# robot.net
KiCad netlist of a schematic drawn in EAGLE
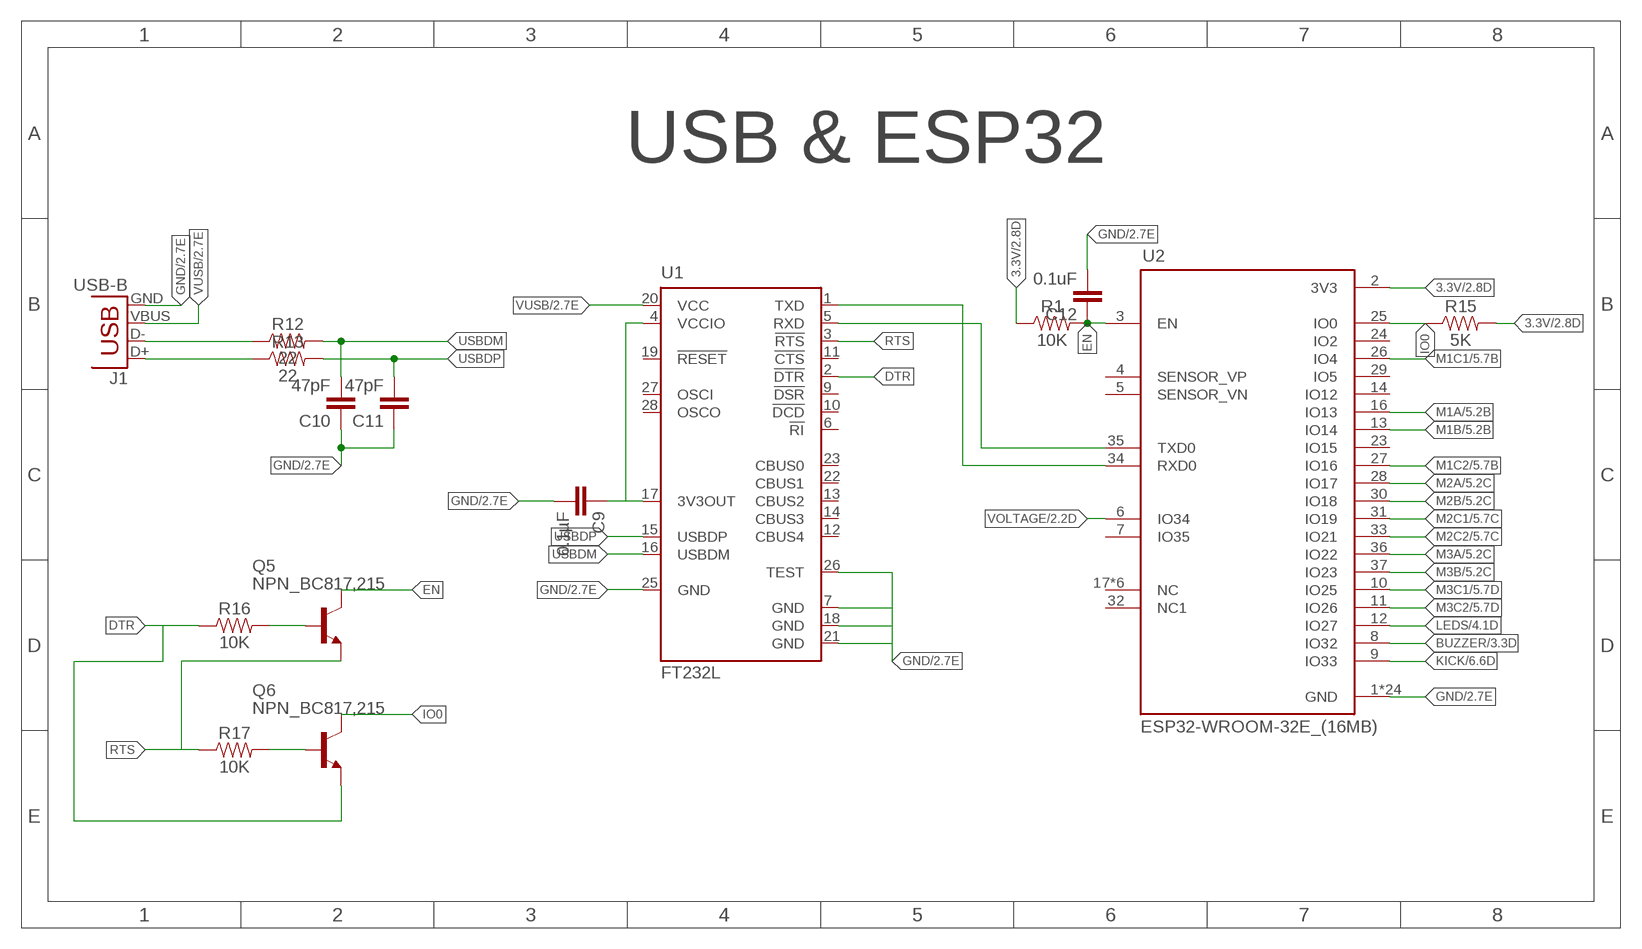
[diagram p0: schematic, sheet 1]
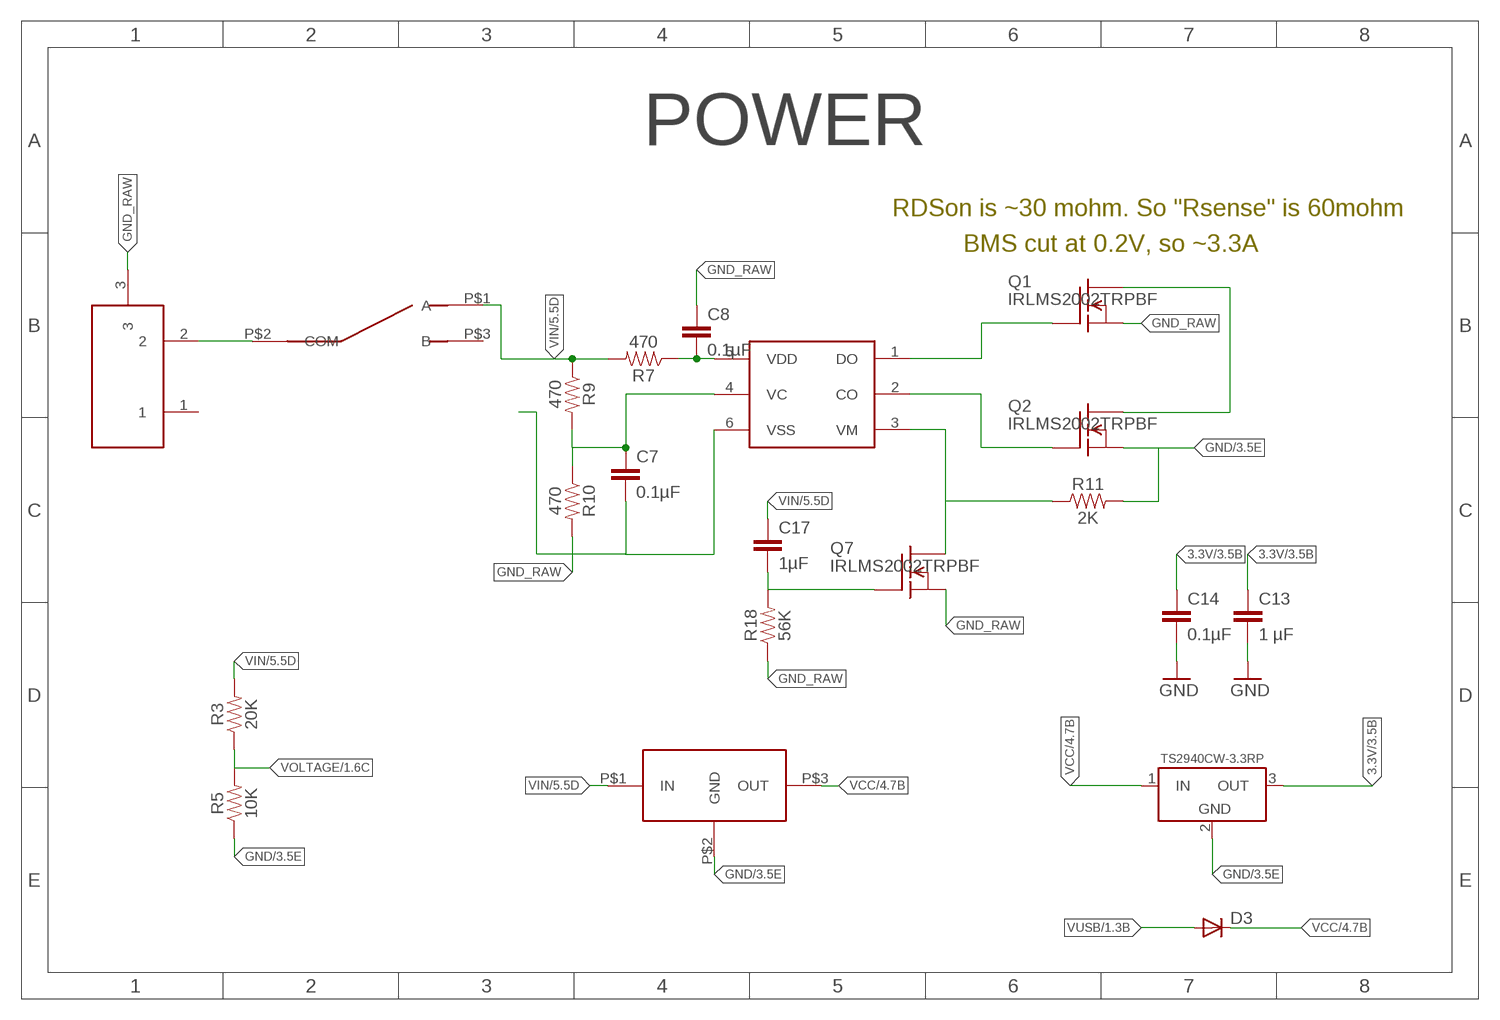
[diagram p1: schematic, sheet 2]
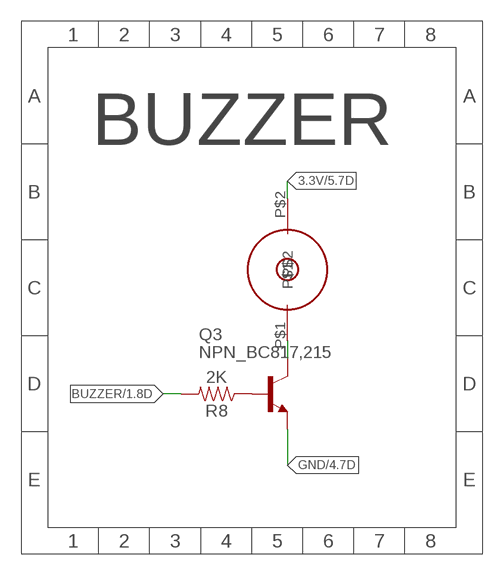
[diagram p2: schematic, sheet 3]
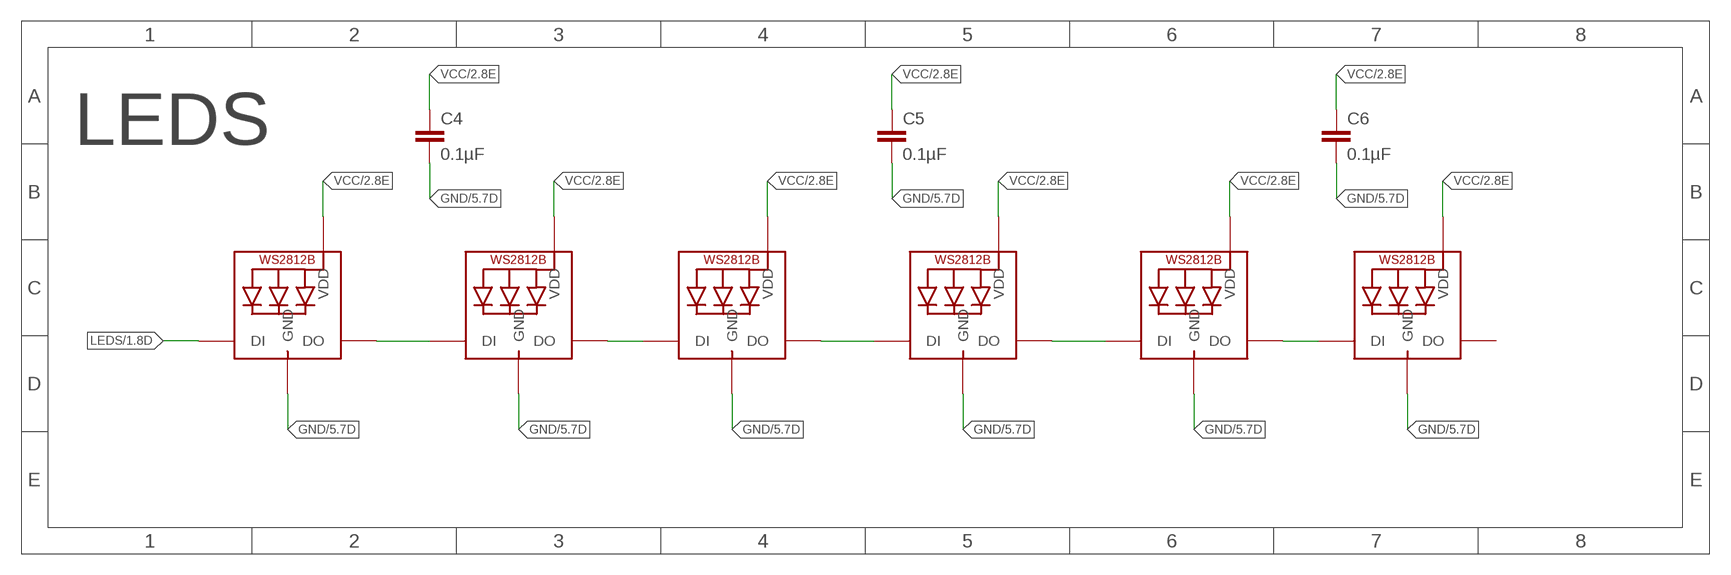
[diagram p3: schematic, sheet 4]
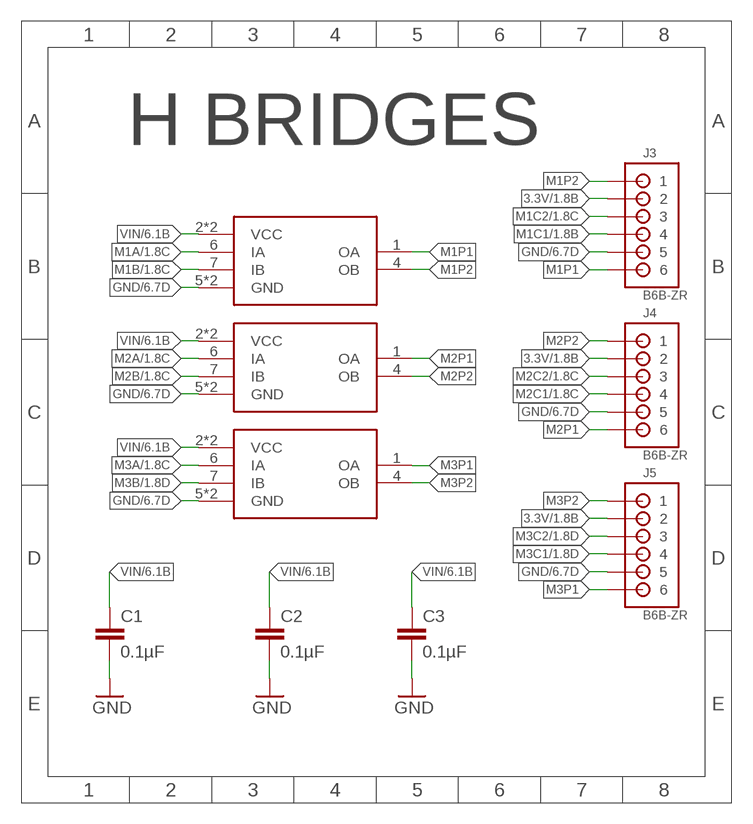
[diagram p4: schematic, sheet 5]
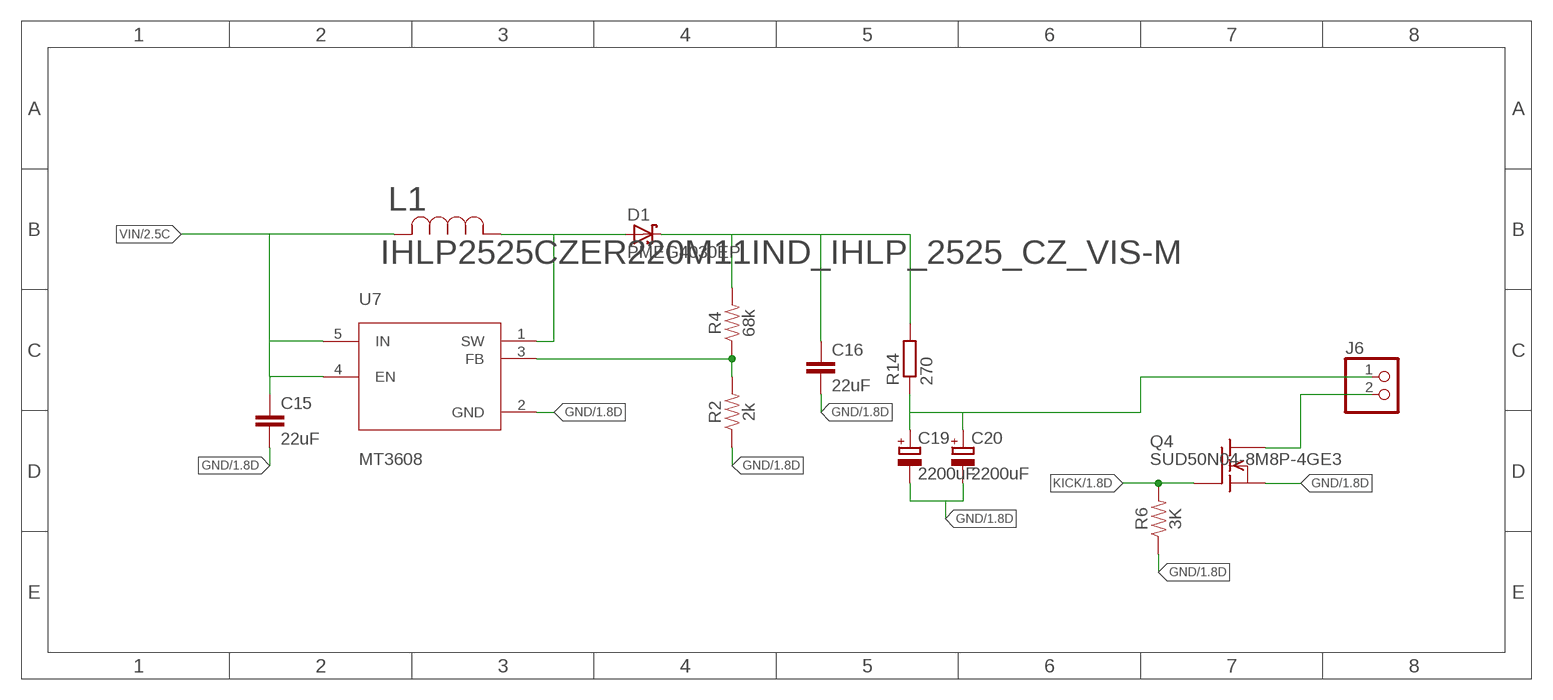
[diagram p5: schematic, sheet 6]

(export (version "E")
  (design (tool "Eeschema 10.0.6"))
  (components
    (comp (ref "C4")
      (value "0.1µF")
      (footprint "eagle-import:0805")
      (libsource (lib "eagle-import") (part "0.33UF/330NF-0805-50V-10%"))
    )
    (comp (ref "C5")
      (value "0.1µF")
      (footprint "eagle-import:0805")
      (fields (field (name "PROD_ID") "CAP-08469"))
      (libsource (lib "eagle-import") (part "0.33UF/330NF-0805-50V-10%"))
    )
    (comp (ref "C6")
      (value "0.1µF")
      (footprint "eagle-import:0805")
      (fields (field (name "PROD_ID") "CAP-08469"))
      (libsource (lib "eagle-import") (part "0.33UF/330NF-0805-50V-10%"))
    )
    (comp (ref "LED1")
      (value "WS2812B5050")
      (footprint "eagle-import:WS2812B")
      (libsource (lib "eagle-import") (part "WS2812B5050"))
    )
    (comp (ref "LED2")
      (value "WS2812B5050")
      (footprint "eagle-import:WS2812B")
      (libsource (lib "eagle-import") (part "WS2812B5050"))
    )
    (comp (ref "LED3")
      (value "WS2812B5050")
      (footprint "eagle-import:WS2812B")
      (libsource (lib "eagle-import") (part "WS2812B5050"))
    )
    (comp (ref "LED4")
      (value "WS2812B5050")
      (footprint "eagle-import:WS2812B")
      (libsource (lib "eagle-import") (part "WS2812B5050"))
    )
    (comp (ref "LED5")
      (value "WS2812B5050")
      (footprint "eagle-import:WS2812B")
      (libsource (lib "eagle-import") (part "WS2812B5050"))
    )
    (comp (ref "LED6")
      (value "WS2812B5050")
      (footprint "eagle-import:WS2812B")
      (libsource (lib "eagle-import") (part "WS2812B5050"))
    )
    (comp (ref "C15")
      (value "22uF")
      (footprint "eagle-import:C0805")
      (libsource (lib "eagle-import") (part "C-EUC0805"))
    )
    (comp (ref "C16")
      (value "22uF")
      (footprint "eagle-import:C0805")
      (libsource (lib "eagle-import") (part "C-EUC0805"))
    )
    (comp (ref "C19")
      (value "2200uF")
      (footprint "eagle-import:E5-13")
      (libsource (lib "eagle-import") (part "CPOL-EUE5-13"))
    )
    (comp (ref "C20")
      (value "2200uF")
      (footprint "eagle-import:E5-13")
      (libsource (lib "eagle-import") (part "CPOL-EUE5-13"))
    )
    (comp (ref "D1")
      (value "PMEG4030EP")
      (footprint "eagle-import:SOD128")
      (libsource (lib "eagle-import") (part "PMEG4030EP"))
    )
    (comp (ref "J6")
      (value "KICKER")
      (footprint "eagle-import:KICKER")
      (libsource (lib "eagle-import") (part "KICKER"))
    )
    (comp (ref "L1")
      (value "IHLP2525CZER220M11IND_IHLP_2525_CZ_VIS-M")
      (footprint "eagle-import:IND_IHLP_2525_CZ_VIS-M")
      (fields (field (name "MANUFACTURER_PART_NUMBER") "IHLP2525CZER220M11"))
      (libsource (lib "eagle-import") (part "IHLP2525CZER220M11IND_IHLP_2525_CZ_VIS-M"))
    )
    (comp (ref "Q4")
      (value "SUD50N04-8M8P-4GE3")
      (footprint "eagle-import:TO252")
      (libsource (lib "eagle-import") (part "SUD50N04-8M8P-4GE3"))
    )
    (comp (ref "R2")
      (value "2k")
      (footprint "eagle-import:0805")
      (libsource (lib "eagle-import") (part "0.3OHM-0805-1/8W-1%"))
    )
    (comp (ref "R4")
      (value "68k")
      (footprint "eagle-import:0805")
      (libsource (lib "eagle-import") (part "0.3OHM-0805-1/8W-1%"))
    )
    (comp (ref "R6")
      (value "3K")
      (footprint "eagle-import:0805")
      (fields (field (name "PROD_ID") "RES-11622"))
      (libsource (lib "eagle-import") (part "0.3OHM-0805-1/8W-1%"))
    )
    (comp (ref "R14")
      (value "270")
      (footprint "eagle-import:R2010")
      (libsource (lib "eagle-import") (part "R-EU_R2010"))
    )
    (comp (ref "U7")
      (value "MT3608")
      (footprint "eagle-import:SOT95P280X145-6N")
      (fields (field (name "MF") "Aerosemi Technology Co., Ltd"))
      (libsource (lib "eagle-import") (part "MT3608"))
    )
    (comp (ref "B1")
      (value "BUZZER66")
      (footprint "eagle-import:BUZZER66")
      (libsource (lib "eagle-import") (part "BUZZER66"))
    )
    (comp (ref "Q3")
      (value "NPN_BC817,215")
      (footprint "eagle-import:SOT-23")
      (libsource (lib "eagle-import") (part "NPN_BC817,215"))
    )
    (comp (ref "R8")
      (value "2K")
      (footprint "eagle-import:0805")
      (libsource (lib "eagle-import") (part "0.3OHM-0805-1/8W-1%"))
    )
    (comp (ref "C7")
      (value "0.1µF")
      (footprint "eagle-import:0805")
      (libsource (lib "eagle-import") (part "0.33UF/330NF-0805-50V-10%"))
    )
    (comp (ref "C8")
      (value "0.1µF")
      (footprint "eagle-import:0805")
      (fields (field (name "PROD_ID") "CAP-08469"))
      (libsource (lib "eagle-import") (part "0.33UF/330NF-0805-50V-10%"))
    )
    (comp (ref "C13")
      (value "1 µF")
      (footprint "eagle-import:0805")
      (fields (field (name "PROD_ID") "CAP-08469"))
      (libsource (lib "eagle-import") (part "0.33UF/330NF-0805-50V-10%"))
    )
    (comp (ref "C14")
      (value "0.1µF")
      (footprint "eagle-import:0805")
      (fields (field (name "PROD_ID") "CAP-08469"))
      (libsource (lib "eagle-import") (part "0.33UF/330NF-0805-50V-10%"))
    )
    (comp (ref "C17")
      (value "1µF")
      (footprint "eagle-import:0805")
      (fields (field (name "PROD_ID") "CAP-08469"))
      (libsource (lib "eagle-import") (part "0.33UF/330NF-0805-50V-10%"))
    )
    (comp (ref "D3")
      (value "DIODESOD")
      (footprint "eagle-import:SOD-323")
      (libsource (lib "eagle-import") (part "DIODESOD"))
    )
    (comp (ref "J2")
      (value "DC21MMX")
      (footprint "eagle-import:DC-21MM")
      (libsource (lib "eagle-import") (part "DC21MMX"))
    )
    (comp (ref "Q1")
      (value "IRLMS2002TRPBF")
      (footprint "eagle-import:SOT23-6")
      (libsource (lib "eagle-import") (part "IRLMS2002TRPBF"))
    )
    (comp (ref "Q2")
      (value "IRLMS2002TRPBF")
      (footprint "eagle-import:SOT23-6")
      (libsource (lib "eagle-import") (part "IRLMS2002TRPBF"))
    )
    (comp (ref "Q7")
      (value "IRLMS2002TRPBF")
      (footprint "eagle-import:SOT23-6")
      (libsource (lib "eagle-import") (part "IRLMS2002TRPBF"))
    )
    (comp (ref "R3")
      (value "20K")
      (footprint "eagle-import:0805")
      (libsource (lib "eagle-import") (part "0.3OHM-0805-1/8W-1%"))
    )
    (comp (ref "R5")
      (value "10K")
      (footprint "eagle-import:0805")
      (libsource (lib "eagle-import") (part "0.3OHM-0805-1/8W-1%"))
    )
    (comp (ref "R7")
      (value "470")
      (footprint "eagle-import:0805")
      (libsource (lib "eagle-import") (part "0.3OHM-0805-1/8W-1%"))
    )
    (comp (ref "R9")
      (value "470")
      (footprint "eagle-import:0805")
      (libsource (lib "eagle-import") (part "0.3OHM-0805-1/8W-1%"))
    )
    (comp (ref "R10")
      (value "470")
      (footprint "eagle-import:0805")
      (libsource (lib "eagle-import") (part "0.3OHM-0805-1/8W-1%"))
    )
    (comp (ref "R11")
      (value "2K")
      (footprint "eagle-import:0805")
      (libsource (lib "eagle-import") (part "0.3OHM-0805-1/8W-1%"))
    )
    (comp (ref "R18")
      (value "56K")
      (footprint "eagle-import:0805")
      (fields (field (name "PROD_ID") "RES-11622"))
      (libsource (lib "eagle-import") (part "0.3OHM-0805-1/8W-1%"))
    )
    (comp (ref "REG1")
      (value "REG_5V")
      (footprint "eagle-import:TRACOPOWER")
      (libsource (lib "eagle-import") (part "REG_5V"))
    )
    (comp (ref "U$1")
      (value "L102011ML04Q")
      (footprint "eagle-import:L102011ML04Q")
      (libsource (lib "eagle-import") (part "L102011ML04Q"))
    )
    (comp (ref "U$25")
      (value "TS2940CW-3.3RP")
      (footprint "eagle-import:SOT223")
      (libsource (lib "eagle-import") (part "TS2940CW-3.3RP"))
    )
    (comp (ref "U3")
      (value "S8252")
      (footprint "eagle-import:SOT23-6")
      (libsource (lib "eagle-import") (part "S8252"))
    )
    (comp (ref "C9")
      (value "0.1µF")
      (footprint "eagle-import:0805")
      (libsource (lib "eagle-import") (part "0.33UF/330NF-0805-50V-10%"))
    )
    (comp (ref "C10")
      (value "47pF")
      (footprint "eagle-import:0805")
      (libsource (lib "eagle-import") (part "CAP0805"))
    )
    (comp (ref "C11")
      (value "47pF")
      (footprint "eagle-import:0805")
      (libsource (lib "eagle-import") (part "CAP0805"))
    )
    (comp (ref "C12")
      (value "0.1uF")
      (footprint "eagle-import:0805")
      (libsource (lib "eagle-import") (part "CAP0805"))
    )
    (comp (ref "J1")
      (value "USB-B")
      (footprint "eagle-import:USB-B-PTH")
      (libsource (lib "eagle-import") (part "USBPTH"))
    )
    (comp (ref "Q5")
      (value "NPN_BC817,215")
      (footprint "eagle-import:SOT-23")
      (libsource (lib "eagle-import") (part "NPN_BC817,215"))
    )
    (comp (ref "Q6")
      (value "NPN_BC817,215")
      (footprint "eagle-import:SOT-23")
      (libsource (lib "eagle-import") (part "NPN_BC817,215"))
    )
    (comp (ref "R1")
      (value "10K")
      (footprint "eagle-import:0805")
      (fields (field (name "PROD_ID") "RES-11622"))
      (libsource (lib "eagle-import") (part "0.3OHM-0805-1/8W-1%"))
    )
    (comp (ref "R12")
      (value "22")
      (footprint "eagle-import:0805")
      (libsource (lib "eagle-import") (part "0.3OHM-0805-1/8W-1%"))
    )
    (comp (ref "R13")
      (value "22")
      (footprint "eagle-import:0805")
      (fields (field (name "PROD_ID") "RES-11622"))
      (libsource (lib "eagle-import") (part "0.3OHM-0805-1/8W-1%"))
    )
    (comp (ref "R15")
      (value "5K")
      (footprint "eagle-import:0805")
      (fields (field (name "PROD_ID") "RES-11622"))
      (libsource (lib "eagle-import") (part "0.3OHM-0805-1/8W-1%"))
    )
    (comp (ref "R16")
      (value "10K")
      (footprint "eagle-import:0805")
      (fields (field (name "PROD_ID") "RES-11622"))
      (libsource (lib "eagle-import") (part "0.3OHM-0805-1/8W-1%"))
    )
    (comp (ref "R17")
      (value "10K")
      (footprint "eagle-import:0805")
      (fields (field (name "PROD_ID") "RES-11622"))
      (libsource (lib "eagle-import") (part "0.3OHM-0805-1/8W-1%"))
    )
    (comp (ref "U1")
      (value "FT232L")
      (footprint "eagle-import:SSOP28")
      (fields (field (name "MPN") "FT232RL"))
      (libsource (lib "eagle-import") (part "FT232L"))
    )
    (comp (ref "U2")
      (value "ESP32-WROOM-32E_(16MB)")
      (footprint "eagle-import:MODULE_ESP32-WROOM-32E_(16MB)")
      (fields (field (name "MF") "Espressif Systems") (field (name "MP") "ESP32-WROOM-32E (16MB)"))
      (libsource (lib "eagle-import") (part "ESP32-WROOM-32E_(16MB)"))
    )
    (comp (ref "C1")
      (value "0.1µF")
      (footprint "eagle-import:0805")
      (libsource (lib "eagle-import") (part "0.33UF/330NF-0805-50V-10%"))
    )
    (comp (ref "C2")
      (value "0.1µF")
      (footprint "eagle-import:0805")
      (fields (field (name "PROD_ID") "CAP-08469"))
      (libsource (lib "eagle-import") (part "0.33UF/330NF-0805-50V-10%"))
    )
    (comp (ref "C3")
      (value "0.1µF")
      (footprint "eagle-import:0805")
      (fields (field (name "PROD_ID") "CAP-08469"))
      (libsource (lib "eagle-import") (part "0.33UF/330NF-0805-50V-10%"))
    )
    (comp (ref "J3")
      (value "B6B-ZR")
      (footprint "eagle-import:B6B-ZR")
      (libsource (lib "eagle-import") (part "B6B-ZR"))
    )
    (comp (ref "J4")
      (value "B6B-ZR")
      (footprint "eagle-import:B6B-ZR")
      (libsource (lib "eagle-import") (part "B6B-ZR"))
    )
    (comp (ref "J5")
      (value "B6B-ZR")
      (footprint "eagle-import:B6B-ZR")
      (libsource (lib "eagle-import") (part "B6B-ZR"))
    )
    (comp (ref "U4")
      (value "L9110")
      (footprint "eagle-import:SO8")
      (libsource (lib "eagle-import") (part "L9110"))
    )
    (comp (ref "U5")
      (value "L9110")
      (footprint "eagle-import:SO8")
      (libsource (lib "eagle-import") (part "L9110"))
    )
    (comp (ref "U6")
      (value "L9110")
      (footprint "eagle-import:SO8")
      (libsource (lib "eagle-import") (part "L9110"))
    )
  )
  (nets
    (net (code "1") (name "1") (class "Default")
      (node (ref "J2") (pin "1") (pinfunction "1_1") (pintype "power_in"))
    )
    (net (code "2") (name "3.3V") (class "Default")
      (node (ref "B1") (pin "P$2") (pinfunction "P$2_P$2") (pintype "bidirectional"))
      (node (ref "C13") (pin "1") (pinfunction "1_1") (pintype "passive"))
      (node (ref "C14") (pin "1") (pinfunction "1_1") (pintype "passive"))
      (node (ref "J3") (pin "2") (pinfunction "2_2") (pintype "bidirectional"))
      (node (ref "J4") (pin "2") (pinfunction "2_2") (pintype "bidirectional"))
      (node (ref "J5") (pin "2") (pinfunction "2_2") (pintype "bidirectional"))
      (node (ref "R1") (pin "1") (pinfunction "1_1") (pintype "passive"))
      (node (ref "R15") (pin "2") (pinfunction "2_2") (pintype "passive"))
      (node (ref "U$25") (pin "3") (pinfunction "OUT_3") (pintype "output"))
      (node (ref "U2") (pin "2") (pinfunction "3V3_2") (pintype "power_in"))
    )
    (net (code "3") (name "BUZZER") (class "Default")
      (node (ref "R8") (pin "2") (pinfunction "2_2") (pintype "passive"))
      (node (ref "U2") (pin "8") (pinfunction "IO32_8") (pintype "bidirectional"))
    )
    (net (code "4") (name "DTR") (class "Default")
      (node (ref "Q6") (pin "2") (pinfunction "E_2") (pintype "passive"))
      (node (ref "R16") (pin "1") (pinfunction "1_1") (pintype "passive"))
      (node (ref "U1") (pin "2") (pinfunction "~{DTR}_2") (pintype "output"))
    )
    (net (code "5") (name "EN") (class "Default")
      (node (ref "C12") (pin "1") (pinfunction "1_1") (pintype "passive"))
      (node (ref "Q5") (pin "3") (pinfunction "C_3") (pintype "passive"))
      (node (ref "R1") (pin "2") (pinfunction "2_2") (pintype "passive"))
      (node (ref "U2") (pin "3") (pinfunction "EN_3") (pintype "input"))
    )
    (net (code "6") (name "GND") (class "Default")
      (node (ref "C1") (pin "2") (pinfunction "2_2") (pintype "passive"))
      (node (ref "C10") (pin "1") (pinfunction "1_1") (pintype "passive"))
      (node (ref "C11") (pin "1") (pinfunction "1_1") (pintype "passive"))
      (node (ref "C12") (pin "2") (pinfunction "2_2") (pintype "passive"))
      (node (ref "C13") (pin "2") (pinfunction "2_2") (pintype "passive"))
      (node (ref "C14") (pin "2") (pinfunction "2_2") (pintype "passive"))
      (node (ref "C15") (pin "2") (pinfunction "2_2") (pintype "passive"))
      (node (ref "C16") (pin "2") (pinfunction "2_2") (pintype "passive"))
      (node (ref "C19") (pin "-") (pinfunction "-_-") (pintype "passive"))
      (node (ref "C2") (pin "2") (pinfunction "2_2") (pintype "passive"))
      (node (ref "C20") (pin "-") (pinfunction "-_-") (pintype "passive"))
      (node (ref "C3") (pin "2") (pinfunction "2_2") (pintype "passive"))
      (node (ref "C4") (pin "2") (pinfunction "2_2") (pintype "passive"))
      (node (ref "C5") (pin "2") (pinfunction "2_2") (pintype "passive"))
      (node (ref "C6") (pin "2") (pinfunction "2_2") (pintype "passive"))
      (node (ref "C9") (pin "2") (pinfunction "2_2") (pintype "passive"))
      (node (ref "J1") (pin "GND") (pinfunction "GND_GND") (pintype "bidirectional"))
      (node (ref "J3") (pin "5") (pinfunction "5_5") (pintype "bidirectional"))
      (node (ref "J4") (pin "5") (pinfunction "5_5") (pintype "bidirectional"))
      (node (ref "J5") (pin "5") (pinfunction "5_5") (pintype "bidirectional"))
      (node (ref "LED1") (pin "3-GND") (pinfunction "GND_3-GND") (pintype "power_in"))
      (node (ref "LED2") (pin "3-GND") (pinfunction "GND_3-GND") (pintype "power_in"))
      (node (ref "LED3") (pin "3-GND") (pinfunction "GND_3-GND") (pintype "power_in"))
      (node (ref "LED4") (pin "3-GND") (pinfunction "GND_3-GND") (pintype "power_in"))
      (node (ref "LED5") (pin "3-GND") (pinfunction "GND_3-GND") (pintype "power_in"))
      (node (ref "LED6") (pin "3-GND") (pinfunction "GND_3-GND") (pintype "power_in"))
      (node (ref "Q2") (pin "4") (pinfunction "S_4") (pintype "passive"))
      (node (ref "Q3") (pin "2") (pinfunction "E_2") (pintype "passive"))
      (node (ref "Q4") (pin "2") (pinfunction "S_2") (pintype "passive"))
      (node (ref "R11") (pin "2") (pinfunction "2_2") (pintype "passive"))
      (node (ref "R2") (pin "1") (pinfunction "1_1") (pintype "passive"))
      (node (ref "R5") (pin "1") (pinfunction "1_1") (pintype "passive"))
      (node (ref "R6") (pin "1") (pinfunction "1_1") (pintype "passive"))
      (node (ref "REG1") (pin "P$2") (pinfunction "GND_P$2") (pintype "bidirectional"))
      (node (ref "U$25") (pin "2") (pinfunction "GND_2") (pintype "power_in"))
      (node (ref "U1") (pin "18") (pinfunction "GND_18") (pintype "power_in"))
      (node (ref "U1") (pin "21") (pinfunction "GND_21") (pintype "power_in"))
      (node (ref "U1") (pin "25") (pinfunction "GND_25") (pintype "power_in"))
      (node (ref "U1") (pin "26") (pinfunction "TEST_26") (pintype "input"))
      (node (ref "U1") (pin "7") (pinfunction "GND_7") (pintype "power_in"))
      (node (ref "U2") (pin "1") (pinfunction "GND_1") (pintype "power_in"))
      (node (ref "U2") (pin "15") (pinfunction "GND_15") (pintype "power_in"))
      (node (ref "U2") (pin "38") (pinfunction "GND_38") (pintype "power_in"))
      (node (ref "U2") (pin "39_1") (pinfunction "GND_39_1") (pintype "power_in"))
      (node (ref "U2") (pin "39_10") (pinfunction "GND_39_10") (pintype "power_in"))
      (node (ref "U2") (pin "39_11") (pinfunction "GND_39_11") (pintype "power_in"))
      (node (ref "U2") (pin "39_12") (pinfunction "GND_39_12") (pintype "power_in"))
      (node (ref "U2") (pin "39_13") (pinfunction "GND_39_13") (pintype "power_in"))
      (node (ref "U2") (pin "39_14") (pinfunction "GND_39_14") (pintype "power_in"))
      (node (ref "U2") (pin "39_15") (pinfunction "GND_39_15") (pintype "power_in"))
      (node (ref "U2") (pin "39_16") (pinfunction "GND_39_16") (pintype "power_in"))
      (node (ref "U2") (pin "39_17") (pinfunction "GND_39_17") (pintype "power_in"))
      (node (ref "U2") (pin "39_18") (pinfunction "GND_39_18") (pintype "power_in"))
      (node (ref "U2") (pin "39_19") (pinfunction "GND_39_19") (pintype "power_in"))
      (node (ref "U2") (pin "39_2") (pinfunction "GND_39_2") (pintype "power_in"))
      (node (ref "U2") (pin "39_20") (pinfunction "GND_39_20") (pintype "power_in"))
      (node (ref "U2") (pin "39_21") (pinfunction "GND_39_21") (pintype "power_in"))
      (node (ref "U2") (pin "39_3") (pinfunction "GND_39_3") (pintype "power_in"))
      (node (ref "U2") (pin "39_4") (pinfunction "GND_39_4") (pintype "power_in"))
      (node (ref "U2") (pin "39_5") (pinfunction "GND_39_5") (pintype "power_in"))
      (node (ref "U2") (pin "39_6") (pinfunction "GND_39_6") (pintype "power_in"))
      (node (ref "U2") (pin "39_7") (pinfunction "GND_39_7") (pintype "power_in"))
      (node (ref "U2") (pin "39_8") (pinfunction "GND_39_8") (pintype "power_in"))
      (node (ref "U2") (pin "39_9") (pinfunction "GND_39_9") (pintype "power_in"))
      (node (ref "U4") (pin "5") (pinfunction "GND_5") (pintype "bidirectional"))
      (node (ref "U4") (pin "8") (pinfunction "GND_8") (pintype "bidirectional"))
      (node (ref "U5") (pin "5") (pinfunction "GND_5") (pintype "bidirectional"))
      (node (ref "U5") (pin "8") (pinfunction "GND_8") (pintype "bidirectional"))
      (node (ref "U6") (pin "5") (pinfunction "GND_5") (pintype "bidirectional"))
      (node (ref "U6") (pin "8") (pinfunction "GND_8") (pintype "bidirectional"))
      (node (ref "U7") (pin "2") (pinfunction "GND_2") (pintype "power_in"))
    )
    (net (code "7") (name "GND_RAW") (class "Default")
      (node (ref "C7") (pin "2") (pinfunction "2_2") (pintype "passive"))
      (node (ref "C8") (pin "1") (pinfunction "1_1") (pintype "passive"))
      (node (ref "J2") (pin "3") (pinfunction "3_3") (pintype "power_in"))
      (node (ref "Q1") (pin "4") (pinfunction "S_4") (pintype "passive"))
      (node (ref "Q7") (pin "4") (pinfunction "S_4") (pintype "passive"))
      (node (ref "R10") (pin "2") (pinfunction "2_2") (pintype "passive"))
      (node (ref "R18") (pin "1") (pinfunction "1_1") (pintype "passive"))
      (node (ref "U3") (pin "6") (pinfunction "VSS_6") (pintype "passive"))
    )
    (net (code "8") (name "IO0") (class "Default")
      (node (ref "Q6") (pin "3") (pinfunction "C_3") (pintype "passive"))
      (node (ref "R15") (pin "1") (pinfunction "1_1") (pintype "passive"))
      (node (ref "U2") (pin "25") (pinfunction "IO0_25") (pintype "bidirectional"))
    )
    (net (code "9") (name "KICK") (class "Default")
      (node (ref "Q4") (pin "1") (pinfunction "G_1") (pintype "passive"))
      (node (ref "R6") (pin "2") (pinfunction "2_2") (pintype "passive"))
      (node (ref "U2") (pin "9") (pinfunction "IO33_9") (pintype "bidirectional"))
    )
    (net (code "10") (name "LEDS") (class "Default")
      (node (ref "LED1") (pin "4-DIN") (pinfunction "DI_4-DIN") (pintype "input"))
      (node (ref "U2") (pin "12") (pinfunction "IO27_12") (pintype "bidirectional"))
    )
    (net (code "11") (name "M1A") (class "Default")
      (node (ref "U2") (pin "16") (pinfunction "IO13_16") (pintype "bidirectional"))
      (node (ref "U4") (pin "6") (pinfunction "IA_6") (pintype "bidirectional"))
    )
    (net (code "12") (name "M1B") (class "Default")
      (node (ref "U2") (pin "13") (pinfunction "IO14_13") (pintype "bidirectional"))
      (node (ref "U4") (pin "7") (pinfunction "IB_7") (pintype "bidirectional"))
    )
    (net (code "13") (name "M1C1") (class "Default")
      (node (ref "J3") (pin "4") (pinfunction "4_4") (pintype "bidirectional"))
      (node (ref "U2") (pin "26") (pinfunction "IO4_26") (pintype "bidirectional"))
    )
    (net (code "14") (name "M1C2") (class "Default")
      (node (ref "J3") (pin "3") (pinfunction "3_3") (pintype "bidirectional"))
      (node (ref "U2") (pin "27") (pinfunction "IO16_27") (pintype "bidirectional"))
    )
    (net (code "15") (name "M1P1") (class "Default")
      (node (ref "J3") (pin "6") (pinfunction "6_6") (pintype "bidirectional"))
      (node (ref "U4") (pin "1") (pinfunction "OA_1") (pintype "bidirectional"))
    )
    (net (code "16") (name "M1P2") (class "Default")
      (node (ref "J3") (pin "1") (pinfunction "1_1") (pintype "bidirectional"))
      (node (ref "U4") (pin "4") (pinfunction "OB_4") (pintype "bidirectional"))
    )
    (net (code "17") (name "M2A") (class "Default")
      (node (ref "U2") (pin "28") (pinfunction "IO17_28") (pintype "bidirectional"))
      (node (ref "U5") (pin "6") (pinfunction "IA_6") (pintype "bidirectional"))
    )
    (net (code "18") (name "M2B") (class "Default")
      (node (ref "U2") (pin "30") (pinfunction "IO18_30") (pintype "bidirectional"))
      (node (ref "U5") (pin "7") (pinfunction "IB_7") (pintype "bidirectional"))
    )
    (net (code "19") (name "M2C1") (class "Default")
      (node (ref "J4") (pin "4") (pinfunction "4_4") (pintype "bidirectional"))
      (node (ref "U2") (pin "31") (pinfunction "IO19_31") (pintype "bidirectional"))
    )
    (net (code "20") (name "M2C2") (class "Default")
      (node (ref "J4") (pin "3") (pinfunction "3_3") (pintype "bidirectional"))
      (node (ref "U2") (pin "33") (pinfunction "IO21_33") (pintype "bidirectional"))
    )
    (net (code "21") (name "M2P1") (class "Default")
      (node (ref "J4") (pin "6") (pinfunction "6_6") (pintype "bidirectional"))
      (node (ref "U5") (pin "1") (pinfunction "OA_1") (pintype "bidirectional"))
    )
    (net (code "22") (name "M2P2") (class "Default")
      (node (ref "J4") (pin "1") (pinfunction "1_1") (pintype "bidirectional"))
      (node (ref "U5") (pin "4") (pinfunction "OB_4") (pintype "bidirectional"))
    )
    (net (code "23") (name "M3A") (class "Default")
      (node (ref "U2") (pin "36") (pinfunction "IO22_36") (pintype "bidirectional"))
      (node (ref "U6") (pin "6") (pinfunction "IA_6") (pintype "bidirectional"))
    )
    (net (code "24") (name "M3B") (class "Default")
      (node (ref "U2") (pin "37") (pinfunction "IO23_37") (pintype "bidirectional"))
      (node (ref "U6") (pin "7") (pinfunction "IB_7") (pintype "bidirectional"))
    )
    (net (code "25") (name "M3C1") (class "Default")
      (node (ref "J5") (pin "4") (pinfunction "4_4") (pintype "bidirectional"))
      (node (ref "U2") (pin "10") (pinfunction "IO25_10") (pintype "bidirectional"))
    )
    (net (code "26") (name "M3C2") (class "Default")
      (node (ref "J5") (pin "3") (pinfunction "3_3") (pintype "bidirectional"))
      (node (ref "U2") (pin "11") (pinfunction "IO26_11") (pintype "bidirectional"))
    )
    (net (code "27") (name "M3P1") (class "Default")
      (node (ref "J5") (pin "6") (pinfunction "6_6") (pintype "bidirectional"))
      (node (ref "U6") (pin "1") (pinfunction "OA_1") (pintype "bidirectional"))
    )
    (net (code "28") (name "M3P2") (class "Default")
      (node (ref "J5") (pin "1") (pinfunction "1_1") (pintype "bidirectional"))
      (node (ref "U6") (pin "4") (pinfunction "OB_4") (pintype "bidirectional"))
    )
    (net (code "29") (name "Net-(C19-Pad+)") (class "Default")
      (node (ref "C19") (pin "+") (pinfunction "+_+") (pintype "passive"))
      (node (ref "C20") (pin "+") (pinfunction "+_+") (pintype "passive"))
      (node (ref "J6") (pin "1") (pinfunction "1_1") (pintype "passive"))
      (node (ref "R14") (pin "1") (pinfunction "1_1") (pintype "passive"))
    )
    (net (code "30") (name "Net-(D1-A)") (class "Default")
      (node (ref "D1") (pin "2") (pinfunction "A_2") (pintype "passive"))
      (node (ref "L1") (pin "1") (pinfunction "1_1") (pintype "passive"))
      (node (ref "U7") (pin "1") (pinfunction "SW_1") (pintype "output"))
    )
    (net (code "31") (name "Net-(D1-K)") (class "Default")
      (node (ref "C16") (pin "1") (pinfunction "1_1") (pintype "passive"))
      (node (ref "D1") (pin "1") (pinfunction "K_1") (pintype "passive"))
      (node (ref "R14") (pin "2") (pinfunction "2_2") (pintype "passive"))
      (node (ref "R4") (pin "2") (pinfunction "2_2") (pintype "passive"))
    )
    (net (code "32") (name "Net-(J1-PadD+)") (class "Default")
      (node (ref "J1") (pin "D+") (pinfunction "D+_D+") (pintype "bidirectional"))
      (node (ref "R13") (pin "1") (pinfunction "1_1") (pintype "passive"))
    )
    (net (code "33") (name "Net-(J1-PadD-)") (class "Default")
      (node (ref "J1") (pin "D-") (pinfunction "D-_D-") (pintype "bidirectional"))
      (node (ref "R12") (pin "1") (pinfunction "1_1") (pintype "passive"))
    )
    (net (code "34") (name "Net-(LED1-DO)") (class "Default")
      (node (ref "LED1") (pin "2-DOUT") (pinfunction "DO_2-DOUT") (pintype "output"))
      (node (ref "LED2") (pin "4-DIN") (pinfunction "DI_4-DIN") (pintype "input"))
    )
    (net (code "35") (name "Net-(LED2-DO)") (class "Default")
      (node (ref "LED2") (pin "2-DOUT") (pinfunction "DO_2-DOUT") (pintype "output"))
      (node (ref "LED3") (pin "4-DIN") (pinfunction "DI_4-DIN") (pintype "input"))
    )
    (net (code "36") (name "Net-(LED3-DO)") (class "Default")
      (node (ref "LED3") (pin "2-DOUT") (pinfunction "DO_2-DOUT") (pintype "output"))
      (node (ref "LED4") (pin "4-DIN") (pinfunction "DI_4-DIN") (pintype "input"))
    )
    (net (code "37") (name "Net-(LED4-DO)") (class "Default")
      (node (ref "LED4") (pin "2-DOUT") (pinfunction "DO_2-DOUT") (pintype "output"))
      (node (ref "LED5") (pin "4-DIN") (pinfunction "DI_4-DIN") (pintype "input"))
    )
    (net (code "38") (name "Net-(LED5-DO)") (class "Default")
      (node (ref "LED5") (pin "2-DOUT") (pinfunction "DO_2-DOUT") (pintype "output"))
      (node (ref "LED6") (pin "4-DIN") (pinfunction "DI_4-DIN") (pintype "input"))
    )
    (net (code "39") (name "Net-(Q1-D-Pad1)") (class "Default")
      (node (ref "Q1") (pin "1") (pinfunction "D_1") (pintype "passive"))
      (node (ref "Q1") (pin "2") (pinfunction "D_2") (pintype "passive"))
      (node (ref "Q1") (pin "5") (pinfunction "D_5") (pintype "passive"))
      (node (ref "Q1") (pin "6") (pinfunction "D_6") (pintype "passive"))
      (node (ref "Q2") (pin "1") (pinfunction "D_1") (pintype "passive"))
      (node (ref "Q2") (pin "2") (pinfunction "D_2") (pintype "passive"))
      (node (ref "Q2") (pin "5") (pinfunction "D_5") (pintype "passive"))
      (node (ref "Q2") (pin "6") (pinfunction "D_6") (pintype "passive"))
    )
    (net (code "40") (name "Net-(Q1-G)") (class "Default")
      (node (ref "Q1") (pin "3") (pinfunction "G_3") (pintype "passive"))
      (node (ref "U3") (pin "1") (pinfunction "DO_1") (pintype "passive"))
    )
    (net (code "41") (name "Net-(Q2-G)") (class "Default")
      (node (ref "Q2") (pin "3") (pinfunction "G_3") (pintype "passive"))
      (node (ref "U3") (pin "2") (pinfunction "CO_2") (pintype "passive"))
    )
    (net (code "42") (name "Net-(Q3-B)") (class "Default")
      (node (ref "Q3") (pin "1") (pinfunction "B_1") (pintype "passive"))
      (node (ref "R8") (pin "1") (pinfunction "1_1") (pintype "passive"))
    )
    (net (code "43") (name "Net-(Q3-C)") (class "Default")
      (node (ref "B1") (pin "P$1") (pinfunction "P$1_P$1") (pintype "bidirectional"))
      (node (ref "Q3") (pin "3") (pinfunction "C_3") (pintype "passive"))
    )
    (net (code "44") (name "Net-(Q4-D)") (class "Default")
      (node (ref "J6") (pin "2") (pinfunction "2_2") (pintype "passive"))
      (node (ref "Q4") (pin "3") (pinfunction "D_3") (pintype "passive"))
    )
    (net (code "45") (name "Net-(Q5-B)") (class "Default")
      (node (ref "Q5") (pin "1") (pinfunction "B_1") (pintype "passive"))
      (node (ref "R16") (pin "2") (pinfunction "2_2") (pintype "passive"))
    )
    (net (code "46") (name "Net-(Q6-B)") (class "Default")
      (node (ref "Q6") (pin "1") (pinfunction "B_1") (pintype "passive"))
      (node (ref "R17") (pin "2") (pinfunction "2_2") (pintype "passive"))
    )
    (net (code "47") (name "Net-(Q7-G)") (class "Default")
      (node (ref "C17") (pin "2") (pinfunction "2_2") (pintype "passive"))
      (node (ref "Q7") (pin "3") (pinfunction "G_3") (pintype "passive"))
      (node (ref "R18") (pin "2") (pinfunction "2_2") (pintype "passive"))
    )
    (net (code "48") (name "Net-(U$1-COM)") (class "Default")
      (node (ref "J2") (pin "2") (pinfunction "2_2") (pintype "power_in"))
      (node (ref "U$1") (pin "P$2") (pinfunction "COM_P$2") (pintype "bidirectional"))
    )
    (net (code "49") (name "Net-(U1-3V3OUT)") (class "Default")
      (node (ref "C9") (pin "1") (pinfunction "1_1") (pintype "passive"))
      (node (ref "U1") (pin "17") (pinfunction "3V3OUT_17") (pintype "output"))
      (node (ref "U1") (pin "4") (pinfunction "VCCIO_4") (pintype "power_in"))
    )
    (net (code "50") (name "Net-(U1-RXD)") (class "Default")
      (node (ref "U1") (pin "5") (pinfunction "RXD_5") (pintype "input"))
      (node (ref "U2") (pin "35") (pinfunction "TXD0_35") (pintype "bidirectional"))
    )
    (net (code "51") (name "Net-(U1-TXD)") (class "Default")
      (node (ref "U1") (pin "1") (pinfunction "TXD_1") (pintype "output"))
      (node (ref "U2") (pin "34") (pinfunction "RXD0_34") (pintype "bidirectional"))
    )
    (net (code "52") (name "Net-(U3-VC)") (class "Default")
      (node (ref "C7") (pin "1") (pinfunction "1_1") (pintype "passive"))
      (node (ref "R10") (pin "1") (pinfunction "1_1") (pintype "passive"))
      (node (ref "R9") (pin "2") (pinfunction "2_2") (pintype "passive"))
      (node (ref "U3") (pin "4") (pinfunction "VC_4") (pintype "passive"))
    )
    (net (code "53") (name "Net-(U3-VDD)") (class "Default")
      (node (ref "C8") (pin "2") (pinfunction "2_2") (pintype "passive"))
      (node (ref "R7") (pin "1") (pinfunction "1_1") (pintype "passive"))
      (node (ref "U3") (pin "5") (pinfunction "VDD_5") (pintype "passive"))
    )
    (net (code "54") (name "Net-(U3-VM)") (class "Default")
      (node (ref "Q7") (pin "1") (pinfunction "D_1") (pintype "passive"))
      (node (ref "Q7") (pin "2") (pinfunction "D_2") (pintype "passive"))
      (node (ref "Q7") (pin "5") (pinfunction "D_5") (pintype "passive"))
      (node (ref "Q7") (pin "6") (pinfunction "D_6") (pintype "passive"))
      (node (ref "R11") (pin "1") (pinfunction "1_1") (pintype "passive"))
      (node (ref "U3") (pin "3") (pinfunction "VM_3") (pintype "passive"))
    )
    (net (code "55") (name "Net-(U7-FB)") (class "Default")
      (node (ref "R2") (pin "2") (pinfunction "2_2") (pintype "passive"))
      (node (ref "R4") (pin "1") (pinfunction "1_1") (pintype "passive"))
      (node (ref "U7") (pin "3") (pinfunction "FB_3") (pintype "input"))
    )
    (net (code "56") (name "RTS") (class "Default")
      (node (ref "Q5") (pin "2") (pinfunction "E_2") (pintype "passive"))
      (node (ref "R17") (pin "1") (pinfunction "1_1") (pintype "passive"))
      (node (ref "U1") (pin "3") (pinfunction "~{RTS}_3") (pintype "output"))
    )
    (net (code "57") (name "USBDM") (class "Default")
      (node (ref "C10") (pin "2") (pinfunction "2_2") (pintype "passive"))
      (node (ref "R12") (pin "2") (pinfunction "2_2") (pintype "passive"))
      (node (ref "U1") (pin "16") (pinfunction "USBDM_16") (pintype "bidirectional"))
    )
    (net (code "58") (name "USBDP") (class "Default")
      (node (ref "C11") (pin "2") (pinfunction "2_2") (pintype "passive"))
      (node (ref "R13") (pin "2") (pinfunction "2_2") (pintype "passive"))
      (node (ref "U1") (pin "15") (pinfunction "USBDP_15") (pintype "bidirectional"))
    )
    (net (code "59") (name "VCC") (class "Default")
      (node (ref "C4") (pin "1") (pinfunction "1_1") (pintype "passive"))
      (node (ref "C5") (pin "1") (pinfunction "1_1") (pintype "passive"))
      (node (ref "C6") (pin "1") (pinfunction "1_1") (pintype "passive"))
      (node (ref "D3") (pin "1") (pinfunction "C_1") (pintype "passive"))
      (node (ref "LED1") (pin "1-VDD") (pinfunction "VDD_1-VDD") (pintype "power_in"))
      (node (ref "LED2") (pin "1-VDD") (pinfunction "VDD_1-VDD") (pintype "power_in"))
      (node (ref "LED3") (pin "1-VDD") (pinfunction "VDD_1-VDD") (pintype "power_in"))
      (node (ref "LED4") (pin "1-VDD") (pinfunction "VDD_1-VDD") (pintype "power_in"))
      (node (ref "LED5") (pin "1-VDD") (pinfunction "VDD_1-VDD") (pintype "power_in"))
      (node (ref "LED6") (pin "1-VDD") (pinfunction "VDD_1-VDD") (pintype "power_in"))
      (node (ref "REG1") (pin "P$3") (pinfunction "OUT_P$3") (pintype "bidirectional"))
      (node (ref "U$25") (pin "1") (pinfunction "IN_1") (pintype "input"))
    )
    (net (code "60") (name "VIN") (class "Default")
      (node (ref "C1") (pin "1") (pinfunction "1_1") (pintype "passive"))
      (node (ref "C15") (pin "1") (pinfunction "1_1") (pintype "passive"))
      (node (ref "C17") (pin "1") (pinfunction "1_1") (pintype "passive"))
      (node (ref "C2") (pin "1") (pinfunction "1_1") (pintype "passive"))
      (node (ref "C3") (pin "1") (pinfunction "1_1") (pintype "passive"))
      (node (ref "L1") (pin "2") (pinfunction "2_2") (pintype "passive"))
      (node (ref "R3") (pin "2") (pinfunction "2_2") (pintype "passive"))
      (node (ref "R7") (pin "2") (pinfunction "2_2") (pintype "passive"))
      (node (ref "R9") (pin "1") (pinfunction "1_1") (pintype "passive"))
      (node (ref "REG1") (pin "P$1") (pinfunction "IN_P$1") (pintype "bidirectional"))
      (node (ref "U$1") (pin "P$1") (pinfunction "A_P$1") (pintype "bidirectional"))
      (node (ref "U4") (pin "2") (pinfunction "VCC_2") (pintype "bidirectional"))
      (node (ref "U4") (pin "3") (pinfunction "VCC_3") (pintype "bidirectional"))
      (node (ref "U5") (pin "2") (pinfunction "VCC_2") (pintype "bidirectional"))
      (node (ref "U5") (pin "3") (pinfunction "VCC_3") (pintype "bidirectional"))
      (node (ref "U6") (pin "2") (pinfunction "VCC_2") (pintype "bidirectional"))
      (node (ref "U6") (pin "3") (pinfunction "VCC_3") (pintype "bidirectional"))
      (node (ref "U7") (pin "4") (pinfunction "EN_4") (pintype "input"))
      (node (ref "U7") (pin "5") (pinfunction "IN_5") (pintype "input"))
    )
    (net (code "61") (name "VOLTAGE") (class "Default")
      (node (ref "R3") (pin "1") (pinfunction "1_1") (pintype "passive"))
      (node (ref "R5") (pin "2") (pinfunction "2_2") (pintype "passive"))
      (node (ref "U2") (pin "6") (pinfunction "IO34_6") (pintype "input"))
    )
    (net (code "62") (name "VUSB") (class "Default")
      (node (ref "D3") (pin "2") (pinfunction "A_2") (pintype "passive"))
      (node (ref "J1") (pin "VBUS") (pinfunction "VBUS_VBUS") (pintype "bidirectional"))
      (node (ref "U1") (pin "20") (pinfunction "VCC_20") (pintype "power_in"))
    )
    (net (code "63") (name "unconnected-(LED6-DO-Pad2-DOUT)") (class "Default")
      (node (ref "LED6") (pin "2-DOUT") (pinfunction "DO_2-DOUT") (pintype "output"))
    )
    (net (code "64") (name "unconnected-(U$1-B-PadP$3)") (class "Default")
      (node (ref "U$1") (pin "P$3") (pinfunction "B_P$3") (pintype "bidirectional"))
    )
    (net (code "65") (name "unconnected-(U1-CBUS0-Pad23)") (class "Default")
      (node (ref "U1") (pin "23") (pinfunction "CBUS0_23") (pintype "bidirectional"))
    )
    (net (code "66") (name "unconnected-(U1-CBUS1-Pad22)") (class "Default")
      (node (ref "U1") (pin "22") (pinfunction "CBUS1_22") (pintype "bidirectional"))
    )
    (net (code "67") (name "unconnected-(U1-CBUS2-Pad13)") (class "Default")
      (node (ref "U1") (pin "13") (pinfunction "CBUS2_13") (pintype "bidirectional"))
    )
    (net (code "68") (name "unconnected-(U1-CBUS3-Pad14)") (class "Default")
      (node (ref "U1") (pin "14") (pinfunction "CBUS3_14") (pintype "bidirectional"))
    )
    (net (code "69") (name "unconnected-(U1-CBUS4-Pad12)") (class "Default")
      (node (ref "U1") (pin "12") (pinfunction "CBUS4_12") (pintype "bidirectional"))
    )
    (net (code "70") (name "unconnected-(U1-OSCI-Pad27)") (class "Default")
      (node (ref "U1") (pin "27") (pinfunction "OSCI_27") (pintype "input"))
    )
    (net (code "71") (name "unconnected-(U1-OSCO-Pad28)") (class "Default")
      (node (ref "U1") (pin "28") (pinfunction "OSCO_28") (pintype "output"))
    )
    (net (code "72") (name "unconnected-(U1-~{CTS}-Pad11)") (class "Default")
      (node (ref "U1") (pin "11") (pinfunction "~{CTS}_11") (pintype "input"))
    )
    (net (code "73") (name "unconnected-(U1-~{DCD}-Pad10)") (class "Default")
      (node (ref "U1") (pin "10") (pinfunction "~{DCD}_10") (pintype "input"))
    )
    (net (code "74") (name "unconnected-(U1-~{DSR}-Pad9)") (class "Default")
      (node (ref "U1") (pin "9") (pinfunction "~{DSR}_9") (pintype "input"))
    )
    (net (code "75") (name "unconnected-(U1-~{RESET}-Pad19)") (class "Default")
      (node (ref "U1") (pin "19") (pinfunction "~{RESET}_19") (pintype "input"))
    )
    (net (code "76") (name "unconnected-(U1-~{RI}-Pad6)") (class "Default")
      (node (ref "U1") (pin "6") (pinfunction "~{RI}_6") (pintype "input"))
    )
    (net (code "77") (name "unconnected-(U2-IO2-Pad24)") (class "Default")
      (node (ref "U2") (pin "24") (pinfunction "IO2_24") (pintype "bidirectional"))
    )
    (net (code "78") (name "unconnected-(U2-IO5-Pad29)") (class "Default")
      (node (ref "U2") (pin "29") (pinfunction "IO5_29") (pintype "bidirectional"))
    )
    (net (code "79") (name "unconnected-(U2-IO12-Pad14)") (class "Default")
      (node (ref "U2") (pin "14") (pinfunction "IO12_14") (pintype "bidirectional"))
    )
    (net (code "80") (name "unconnected-(U2-IO15-Pad23)") (class "Default")
      (node (ref "U2") (pin "23") (pinfunction "IO15_23") (pintype "bidirectional"))
    )
    (net (code "81") (name "unconnected-(U2-IO35-Pad7)") (class "Default")
      (node (ref "U2") (pin "7") (pinfunction "IO35_7") (pintype "input"))
    )
    (net (code "82") (name "unconnected-(U2-NC-Pad17)") (class "Default")
      (node (ref "U2") (pin "17") (pinfunction "NC_17") (pintype "no_connect"))
    )
    (net (code "83") (name "unconnected-(U2-NC-Pad18)") (class "Default")
      (node (ref "U2") (pin "18") (pinfunction "NC_18") (pintype "no_connect"))
    )
    (net (code "84") (name "unconnected-(U2-NC-Pad19)") (class "Default")
      (node (ref "U2") (pin "19") (pinfunction "NC_19") (pintype "no_connect"))
    )
    (net (code "85") (name "unconnected-(U2-NC-Pad20)") (class "Default")
      (node (ref "U2") (pin "20") (pinfunction "NC_20") (pintype "no_connect"))
    )
    (net (code "86") (name "unconnected-(U2-NC-Pad21)") (class "Default")
      (node (ref "U2") (pin "21") (pinfunction "NC_21") (pintype "no_connect"))
    )
    (net (code "87") (name "unconnected-(U2-NC-Pad22)") (class "Default")
      (node (ref "U2") (pin "22") (pinfunction "NC_22") (pintype "no_connect"))
    )
    (net (code "88") (name "unconnected-(U2-NC1-Pad32)") (class "Default")
      (node (ref "U2") (pin "32") (pinfunction "NC1_32") (pintype "no_connect"))
    )
    (net (code "89") (name "unconnected-(U2-SENSOR_VN-Pad5)") (class "Default")
      (node (ref "U2") (pin "5") (pinfunction "SENSOR_VN_5") (pintype "input"))
    )
    (net (code "90") (name "unconnected-(U2-SENSOR_VP-Pad4)") (class "Default")
      (node (ref "U2") (pin "4") (pinfunction "SENSOR_VP_4") (pintype "input"))
    )
  )
)
